# ACCEL.net
KiCad netlist of a schematic drawn in Altium Designer
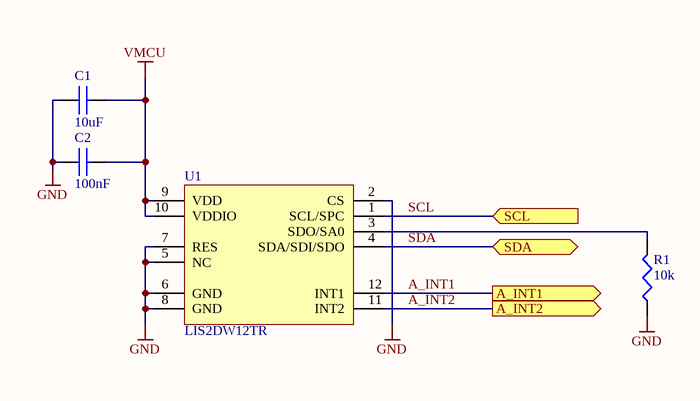
[diagram p0: ACCEL.SchDoc]

(export (version "E")
  (design (tool "Eeschema 10.0.6"))
  (components
    (comp (ref "C1")
      (value "10uF")
      (footprint "CAP0603")
      (description "Cap Ceramic 10uF 10V X5R 10% SMD 0603 85C Paper T/R")
      (fields
        (field (name "MANUFACTURER") "Samsung")
        (field (name "MANUFACTURER PART NUMBER") "CL10A106KP8NNNC")
      )
      (libsource (lib "Passive") (part "C - 10uF/10V"))
    )
    (comp (ref "C2")
      (value "100nF")
      (footprint "CAP0402")
      (fields
        (field (name "MANUFACTURER") "Multicomp")
        (field (name "MANUFACTURER PART NUMBER") "MC0402X104J160CT")
        (field (name "TOLERANCE") "5%")
      )
      (libsource (lib "Passive") (part "C - 100nF/0402"))
    )
    (comp (ref "R1")
      (value "10k")
      (footprint "RES0402")
      (fields
        (field (name "MANUFACTURER") "Multicomp")
        (field (name "MANUFACTURER PART NUMBER") "MCWR04X1002FTL")
        (field (name "TOLERANCE") "1%")
      )
      (libsource (lib "Passive") (part "R - 10k/0402"))
    )
    (comp (ref "U1")
      (value "LIS2DW12TR")
      (footprint "LGA-12")
      (description "MEMS Accelerometer, Digital, X, Y, Z, ± 2g, ± 4g, ± 8g, ± 16g, 1.62 V, 3.6 V")
      (fields
        (field (name "MANUFACTURER") "TDK InvenSense")
        (field (name "MANUFACTURER PART NUMBER") "MPU-9250")
      )
      (libsource (lib "Active") (part "SEN - LIS2DW12TR"))
    )
  )
  (nets
    (net (code "1") (name "/A_INT1") (class "Default")
      (node (ref "U1") (pin "12") (pinfunction "INT1_12") (pintype "passive"))
    )
    (net (code "2") (name "/A_INT2") (class "Default")
      (node (ref "U1") (pin "11") (pinfunction "INT2_11") (pintype "passive"))
    )
    (net (code "3") (name "/SCL") (class "Default")
      (node (ref "U1") (pin "1") (pinfunction "SCL/SPC_1") (pintype "passive"))
    )
    (net (code "4") (name "/SDA") (class "Default")
      (node (ref "U1") (pin "4") (pinfunction "SDA/SDI/SDO_4") (pintype "passive"))
    )
    (net (code "5") (name "GND") (class "Default")
      (node (ref "C1") (pin "1") (pinfunction "1_1") (pintype "passive"))
      (node (ref "C2") (pin "1") (pinfunction "1_1") (pintype "passive"))
      (node (ref "R1") (pin "1") (pinfunction "1_1") (pintype "passive"))
      (node (ref "U1") (pin "2") (pinfunction "CS_2") (pintype "passive"))
      (node (ref "U1") (pin "5") (pinfunction "NC_5") (pintype "passive"))
      (node (ref "U1") (pin "6") (pinfunction "GND_6") (pintype "passive"))
      (node (ref "U1") (pin "7") (pinfunction "RES_7") (pintype "passive"))
      (node (ref "U1") (pin "8") (pinfunction "GND_8") (pintype "passive"))
    )
    (net (code "6") (name "Net-(U1-SDO{slash}SA0)") (class "Default")
      (node (ref "R1") (pin "2") (pinfunction "2_2") (pintype "passive"))
      (node (ref "U1") (pin "3") (pinfunction "SDO/SA0_3") (pintype "passive"))
    )
    (net (code "7") (name "VMCU") (class "Default")
      (node (ref "C1") (pin "2") (pinfunction "2_2") (pintype "passive"))
      (node (ref "C2") (pin "2") (pinfunction "2_2") (pintype "passive"))
      (node (ref "U1") (pin "10") (pinfunction "VDDIO_10") (pintype "passive"))
      (node (ref "U1") (pin "9") (pinfunction "VDD_9") (pintype "passive"))
    )
  )
)
